# bbb_d300_breakout.net
KiCad netlist of a schematic drawn in EAGLE
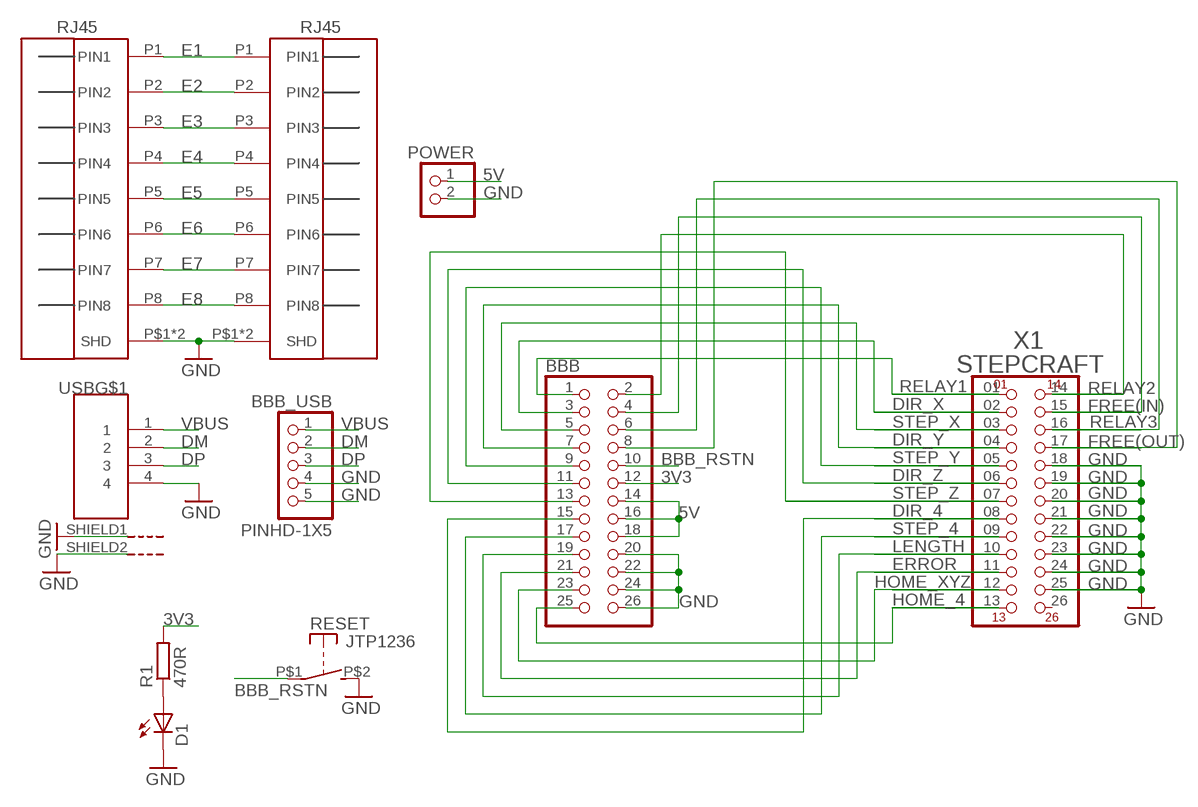
[diagram p0: schematic, sheet 1]
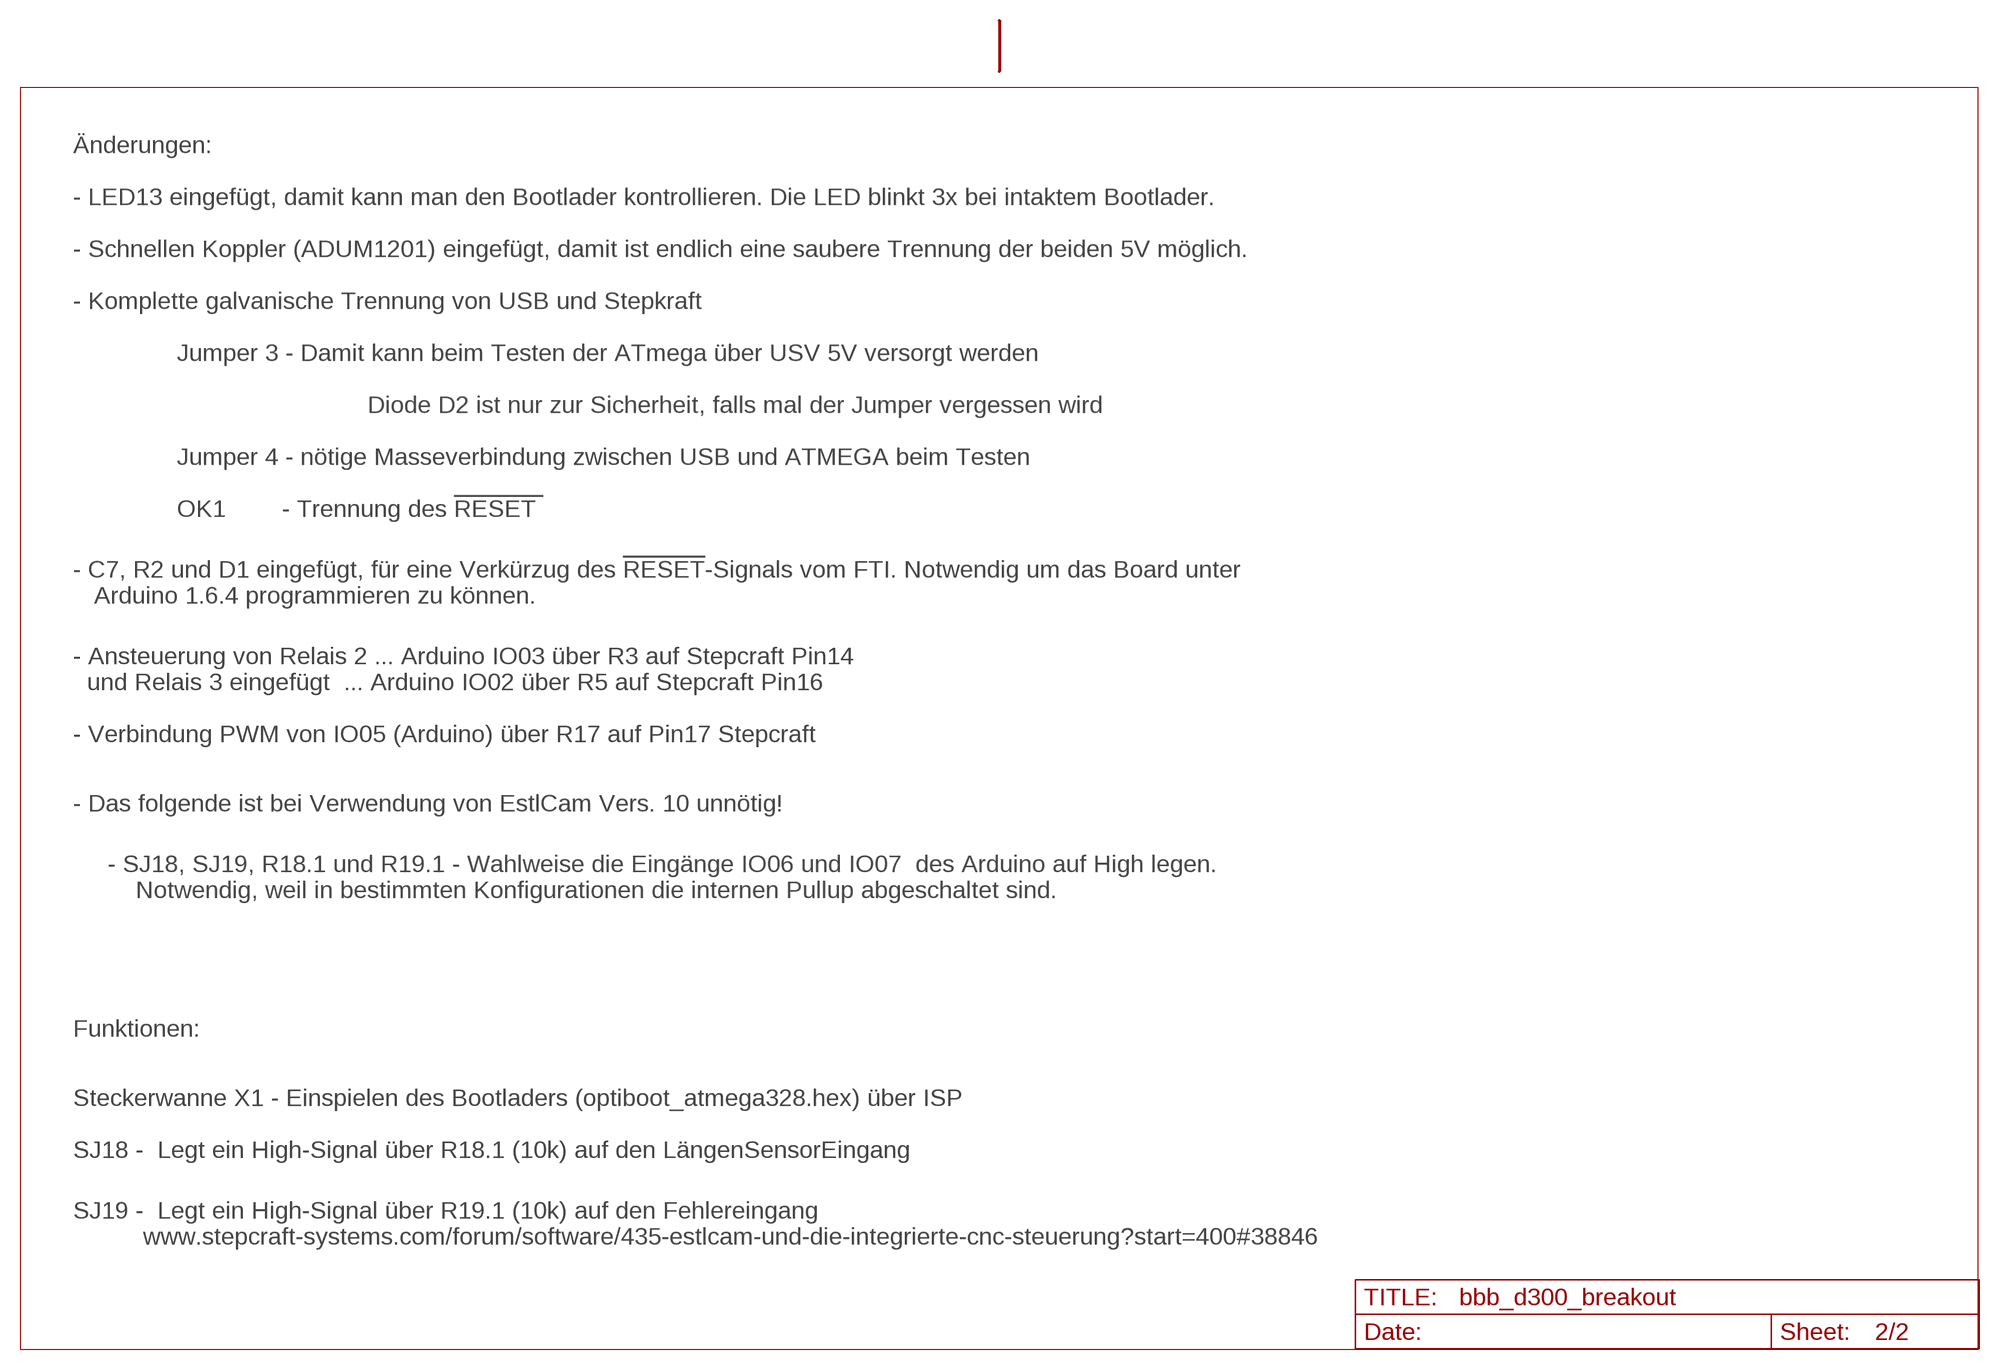
[diagram p1: schematic, sheet 2]

(export (version "E")
  (design (tool "Eeschema 10.0.6"))
  (components
    (comp (ref "BBB")
      (value "PINHD-2X13")
      (footprint "eagle-import:2X13")
      (libsource (lib "eagle-import") (part "PINHD-2X13"))
    )
    (comp (ref "BBB_USB")
      (value "PINHD-1X5")
      (footprint "eagle-import:1X05_XXL")
      (libsource (lib "eagle-import") (part "PINHD-1X5"))
    )
    (comp (ref "D1")
      (value "LEDXXL")
      (footprint "eagle-import:LED3MM_XXL")
      (libsource (lib "eagle-import") (part "LEDXXL"))
    )
    (comp (ref "POWER")
      (value "PINHD-1X2")
      (footprint "eagle-import:1X02")
      (libsource (lib "eagle-import") (part "PINHD-1X2"))
    )
    (comp (ref "R1")
      (value "470R")
      (footprint "eagle-import:R0805")
      (libsource (lib "eagle-import") (part "R-EU_R0805"))
    )
    (comp (ref "RESET")
      (value "JTP1236")
      (footprint "eagle-import:JTP1236")
      (libsource (lib "eagle-import") (part "JTP1236"))
    )
    (comp (ref "USB")
      (value "USB_HOST")
      (footprint "eagle-import:USB")
      (libsource (lib "eagle-import") (part "USB_HOST"))
    )
    (comp (ref "X1")
      (value "STEPCRAFT")
      (footprint "eagle-import:2X13_90_STEPCRAFT")
      (libsource (lib "eagle-import") (part "PINHD-2X13_STEPCRAFT"))
    )
    (comp (ref "X2")
      (value "RJ45")
      (footprint "eagle-import:RJ45")
      (libsource (lib "eagle-import") (part "RJ45"))
    )
    (comp (ref "X3")
      (value "RJ45")
      (footprint "eagle-import:RJ45")
      (libsource (lib "eagle-import") (part "RJ45"))
    )
  )
  (nets
    (net (code "1") (name "3V3") (class "Default")
      (node (ref "BBB") (pin "12") (pinfunction "12_12") (pintype "passive"))
      (node (ref "R1") (pin "2") (pinfunction "2_2") (pintype "passive"))
    )
    (net (code "2") (name "5V") (class "Default")
      (node (ref "BBB") (pin "14") (pinfunction "14_14") (pintype "passive"))
      (node (ref "BBB") (pin "16") (pinfunction "16_16") (pintype "passive"))
      (node (ref "BBB") (pin "18") (pinfunction "18_18") (pintype "passive"))
      (node (ref "POWER") (pin "1") (pinfunction "1_1") (pintype "passive"))
    )
    (net (code "3") (name "BBB_RSTN") (class "Default")
      (node (ref "BBB") (pin "10") (pinfunction "10_10") (pintype "passive"))
      (node (ref "RESET") (pin "P$1") (pinfunction "P_P$1") (pintype "passive"))
    )
    (net (code "4") (name "DIR_4") (class "Default")
      (node (ref "BBB") (pin "15") (pinfunction "15_15") (pintype "passive"))
      (node (ref "X1") (pin "08") (pinfunction "8_08") (pintype "passive"))
    )
    (net (code "5") (name "DIR_X") (class "Default")
      (node (ref "BBB") (pin "3") (pinfunction "3_3") (pintype "passive"))
      (node (ref "X1") (pin "02") (pinfunction "2_02") (pintype "passive"))
    )
    (net (code "6") (name "DIR_Y") (class "Default")
      (node (ref "BBB") (pin "7") (pinfunction "7_7") (pintype "passive"))
      (node (ref "X1") (pin "04") (pinfunction "4_04") (pintype "passive"))
    )
    (net (code "7") (name "DIR_Z") (class "Default")
      (node (ref "BBB") (pin "11") (pinfunction "11_11") (pintype "passive"))
      (node (ref "X1") (pin "06") (pinfunction "6_06") (pintype "passive"))
    )
    (net (code "8") (name "DM") (class "Default")
      (node (ref "BBB_USB") (pin "2") (pinfunction "2_2") (pintype "passive"))
      (node (ref "USB") (pin "2") (pinfunction "2_2") (pintype "passive"))
    )
    (net (code "9") (name "DP") (class "Default")
      (node (ref "BBB_USB") (pin "3") (pinfunction "3_3") (pintype "passive"))
      (node (ref "USB") (pin "3") (pinfunction "3_3") (pintype "passive"))
    )
    (net (code "10") (name "E1") (class "Default")
      (node (ref "X2") (pin "P1") (pinfunction "PIN1_P1") (pintype "bidirectional"))
      (node (ref "X3") (pin "P1") (pinfunction "PIN1_P1") (pintype "bidirectional"))
    )
    (net (code "11") (name "E2") (class "Default")
      (node (ref "X2") (pin "P2") (pinfunction "PIN2_P2") (pintype "bidirectional"))
      (node (ref "X3") (pin "P2") (pinfunction "PIN2_P2") (pintype "bidirectional"))
    )
    (net (code "12") (name "E3") (class "Default")
      (node (ref "X2") (pin "P3") (pinfunction "PIN3_P3") (pintype "bidirectional"))
      (node (ref "X3") (pin "P3") (pinfunction "PIN3_P3") (pintype "bidirectional"))
    )
    (net (code "13") (name "E4") (class "Default")
      (node (ref "X2") (pin "P4") (pinfunction "PIN4_P4") (pintype "bidirectional"))
      (node (ref "X3") (pin "P4") (pinfunction "PIN4_P4") (pintype "bidirectional"))
    )
    (net (code "14") (name "E5") (class "Default")
      (node (ref "X2") (pin "P5") (pinfunction "PIN5_P5") (pintype "bidirectional"))
      (node (ref "X3") (pin "P5") (pinfunction "PIN5_P5") (pintype "bidirectional"))
    )
    (net (code "15") (name "E6") (class "Default")
      (node (ref "X2") (pin "P6") (pinfunction "PIN6_P6") (pintype "bidirectional"))
      (node (ref "X3") (pin "P6") (pinfunction "PIN6_P6") (pintype "bidirectional"))
    )
    (net (code "16") (name "E7") (class "Default")
      (node (ref "X2") (pin "P7") (pinfunction "PIN7_P7") (pintype "bidirectional"))
      (node (ref "X3") (pin "P7") (pinfunction "PIN7_P7") (pintype "bidirectional"))
    )
    (net (code "17") (name "E8") (class "Default")
      (node (ref "X2") (pin "P8") (pinfunction "PIN8_P8") (pintype "bidirectional"))
      (node (ref "X3") (pin "P8") (pinfunction "PIN8_P8") (pintype "bidirectional"))
    )
    (net (code "18") (name "ERROR") (class "Default")
      (node (ref "BBB") (pin "21") (pinfunction "21_21") (pintype "passive"))
      (node (ref "X1") (pin "11") (pinfunction "11_11") (pintype "passive"))
    )
    (net (code "19") (name "FREE(IN)") (class "Default")
      (node (ref "BBB") (pin "4") (pinfunction "4_4") (pintype "passive"))
      (node (ref "X1") (pin "15") (pinfunction "15_15") (pintype "passive"))
    )
    (net (code "20") (name "FREE(OUT)") (class "Default")
      (node (ref "BBB") (pin "8") (pinfunction "8_8") (pintype "passive"))
      (node (ref "X1") (pin "17") (pinfunction "17_17") (pintype "passive"))
    )
    (net (code "21") (name "GND") (class "Default")
      (node (ref "BBB") (pin "20") (pinfunction "20_20") (pintype "passive"))
      (node (ref "BBB") (pin "22") (pinfunction "22_22") (pintype "passive"))
      (node (ref "BBB") (pin "24") (pinfunction "24_24") (pintype "passive"))
      (node (ref "BBB") (pin "26") (pinfunction "26_26") (pintype "passive"))
      (node (ref "BBB_USB") (pin "4") (pinfunction "4_4") (pintype "passive"))
      (node (ref "BBB_USB") (pin "5") (pinfunction "5_5") (pintype "passive"))
      (node (ref "D1") (pin "K") (pinfunction "C_K") (pintype "passive"))
      (node (ref "POWER") (pin "2") (pinfunction "2_2") (pintype "passive"))
      (node (ref "RESET") (pin "P$2") (pinfunction "S_P$2") (pintype "passive"))
      (node (ref "USB") (pin "4") (pinfunction "4_4") (pintype "passive"))
      (node (ref "USB") (pin "SHIELD1") (pinfunction "G_SHIELD1") (pintype "passive"))
      (node (ref "USB") (pin "SHIELD2") (pinfunction "G_SHIELD2") (pintype "passive"))
      (node (ref "X1") (pin "18") (pinfunction "18_18") (pintype "passive"))
      (node (ref "X1") (pin "19") (pinfunction "19_19") (pintype "passive"))
      (node (ref "X1") (pin "20") (pinfunction "20_20") (pintype "passive"))
      (node (ref "X1") (pin "21") (pinfunction "21_21") (pintype "passive"))
      (node (ref "X1") (pin "22") (pinfunction "22_22") (pintype "passive"))
      (node (ref "X1") (pin "23") (pinfunction "23_23") (pintype "passive"))
      (node (ref "X1") (pin "24") (pinfunction "24_24") (pintype "passive"))
      (node (ref "X1") (pin "25") (pinfunction "25_25") (pintype "passive"))
      (node (ref "X2") (pin "P$1") (pinfunction "SHD_P$1") (pintype "bidirectional"))
      (node (ref "X2") (pin "P$2") (pinfunction "SHD_P$2") (pintype "bidirectional"))
      (node (ref "X3") (pin "P$1") (pinfunction "SHD_P$1") (pintype "bidirectional"))
      (node (ref "X3") (pin "P$2") (pinfunction "SHD_P$2") (pintype "bidirectional"))
    )
    (net (code "22") (name "HOME_4") (class "Default")
      (node (ref "BBB") (pin "25") (pinfunction "25_25") (pintype "passive"))
      (node (ref "X1") (pin "13") (pinfunction "13_13") (pintype "passive"))
    )
    (net (code "23") (name "HOME_XYZ") (class "Default")
      (node (ref "BBB") (pin "23") (pinfunction "23_23") (pintype "passive"))
      (node (ref "X1") (pin "12") (pinfunction "12_12") (pintype "passive"))
    )
    (net (code "24") (name "LENGTH") (class "Default")
      (node (ref "BBB") (pin "19") (pinfunction "19_19") (pintype "passive"))
      (node (ref "X1") (pin "10") (pinfunction "10_10") (pintype "passive"))
    )
    (net (code "25") (name "Net-(D1-PadA)") (class "Default")
      (node (ref "D1") (pin "A") (pinfunction "A_A") (pintype "passive"))
      (node (ref "R1") (pin "1") (pinfunction "1_1") (pintype "passive"))
    )
    (net (code "26") (name "RELAY1") (class "Default")
      (node (ref "BBB") (pin "1") (pinfunction "1_1") (pintype "passive"))
      (node (ref "X1") (pin "01") (pinfunction "1_01") (pintype "passive"))
    )
    (net (code "27") (name "RELAY2") (class "Default")
      (node (ref "BBB") (pin "2") (pinfunction "2_2") (pintype "passive"))
      (node (ref "X1") (pin "14") (pinfunction "14_14") (pintype "passive"))
    )
    (net (code "28") (name "RELAY3") (class "Default")
      (node (ref "BBB") (pin "6") (pinfunction "6_6") (pintype "passive"))
      (node (ref "X1") (pin "16") (pinfunction "16_16") (pintype "passive"))
    )
    (net (code "29") (name "STEP_4") (class "Default")
      (node (ref "BBB") (pin "17") (pinfunction "17_17") (pintype "passive"))
      (node (ref "X1") (pin "09") (pinfunction "9_09") (pintype "passive"))
    )
    (net (code "30") (name "STEP_X") (class "Default")
      (node (ref "BBB") (pin "5") (pinfunction "5_5") (pintype "passive"))
      (node (ref "X1") (pin "03") (pinfunction "3_03") (pintype "passive"))
    )
    (net (code "31") (name "STEP_Y") (class "Default")
      (node (ref "BBB") (pin "9") (pinfunction "9_9") (pintype "passive"))
      (node (ref "X1") (pin "05") (pinfunction "5_05") (pintype "passive"))
    )
    (net (code "32") (name "STEP_Z") (class "Default")
      (node (ref "BBB") (pin "13") (pinfunction "13_13") (pintype "passive"))
      (node (ref "X1") (pin "07") (pinfunction "7_07") (pintype "passive"))
    )
    (net (code "33") (name "VBUS") (class "Default")
      (node (ref "BBB_USB") (pin "1") (pinfunction "1_1") (pintype "passive"))
      (node (ref "USB") (pin "1") (pinfunction "1_1") (pintype "passive"))
    )
    (net (code "34") (name "unconnected-(X1-Pad26)") (class "Default")
      (node (ref "X1") (pin "26") (pinfunction "26_26") (pintype "passive"))
    )
  )
)
